# MPL3115A2_v10sch.net
KiCad netlist of a schematic drawn in EAGLE
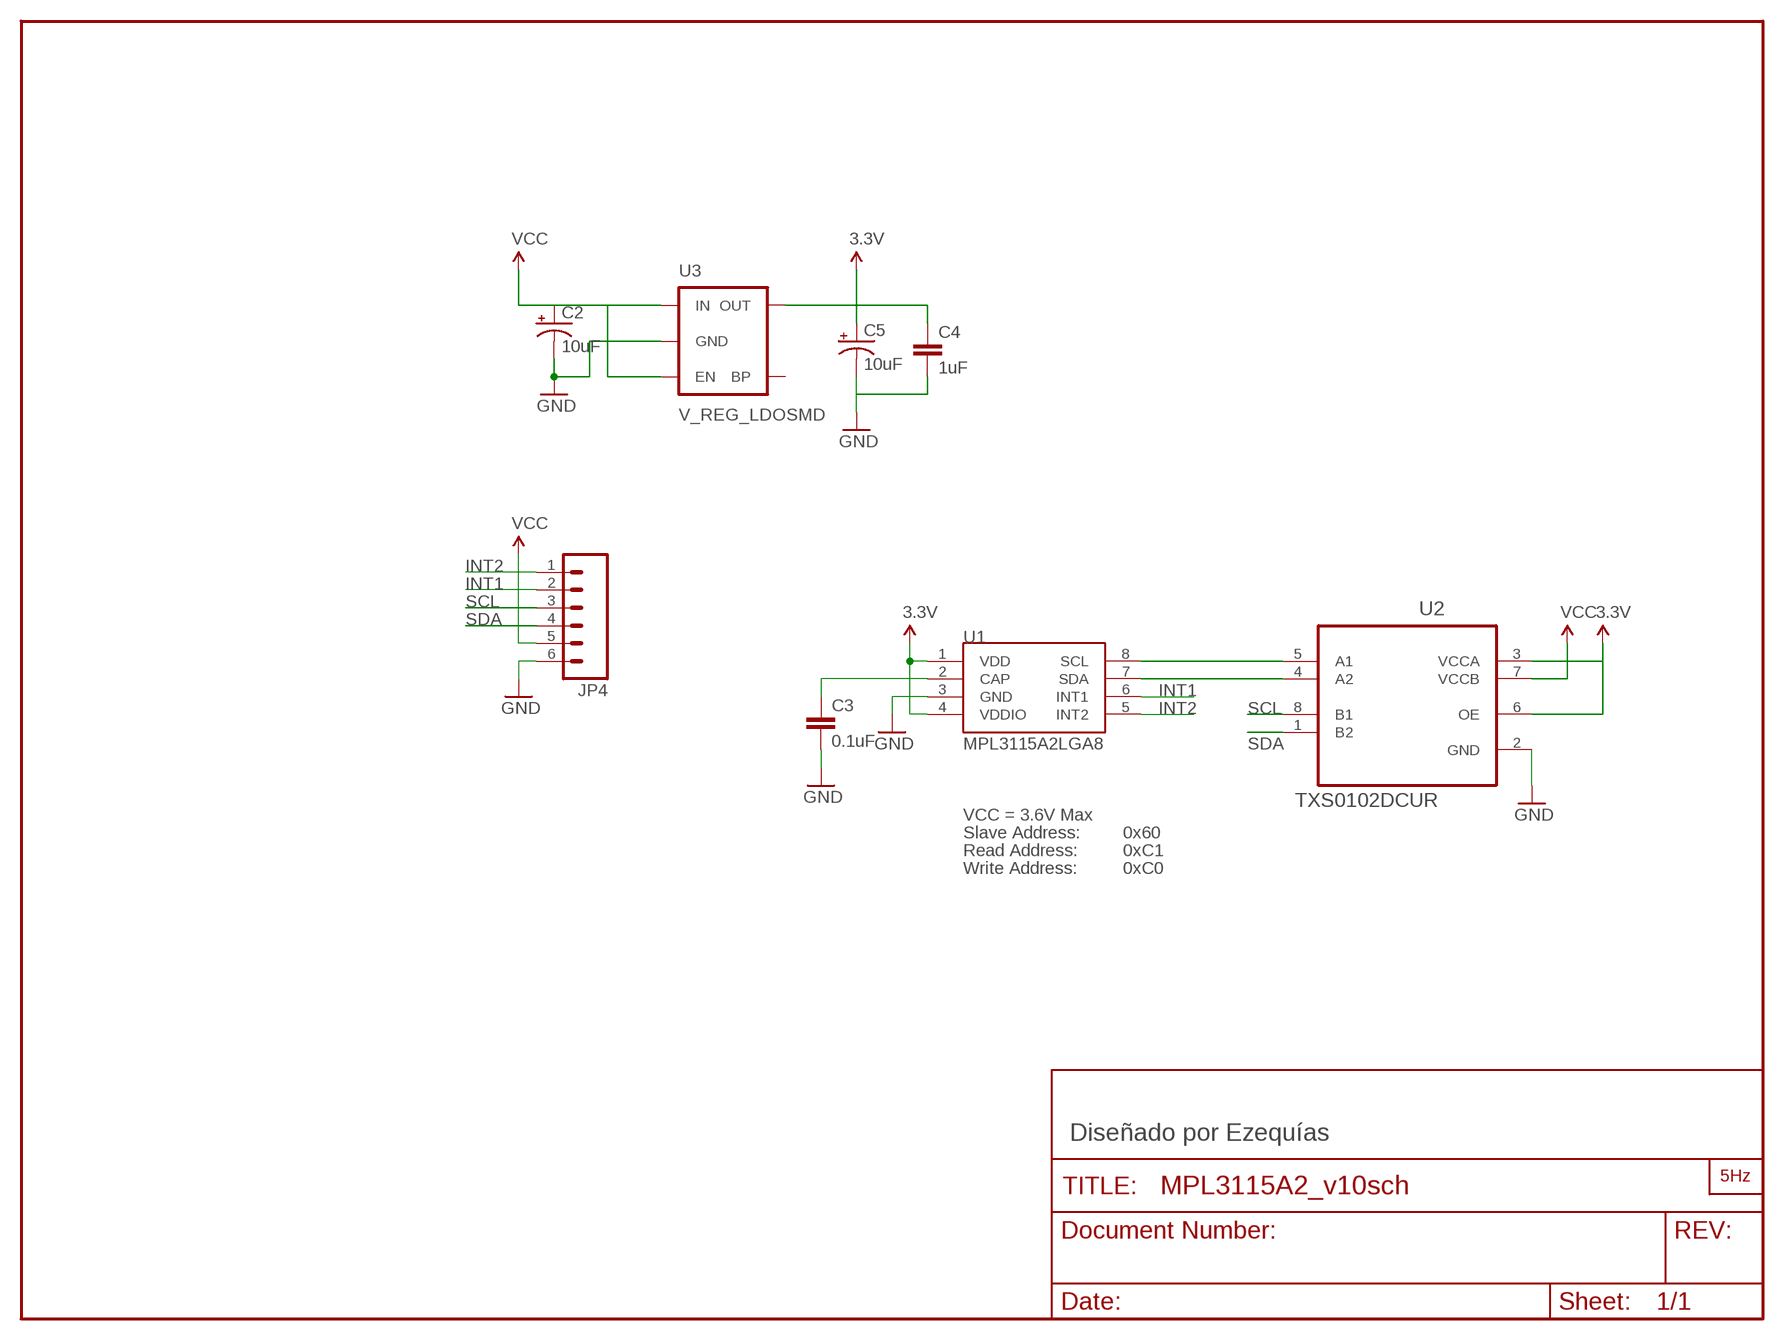
[diagram p0: schematic, sheet 1]

(export (version "E")
  (design (tool "Eeschema 10.0.6"))
  (components
    (comp (ref "C2")
      (value "10uF")
      (footprint "eagle-import:EIA3216")
      (libsource (lib "eagle-import") (part "CAP_POL1206"))
    )
    (comp (ref "C3")
      (value "0.1uF")
      (footprint "eagle-import:0402-CAP")
      (libsource (lib "eagle-import") (part "CAP0402-CAP"))
    )
    (comp (ref "C4")
      (value "1uF")
      (footprint "eagle-import:0402-CAP")
      (libsource (lib "eagle-import") (part "CAP0402-CAP"))
    )
    (comp (ref "C5")
      (value "10uF")
      (footprint "eagle-import:EIA3216")
      (libsource (lib "eagle-import") (part "CAP_POL1206"))
    )
    (comp (ref "JP4")
      (value "M06SIP")
      (footprint "eagle-import:1X06")
      (libsource (lib "eagle-import") (part "M06SIP"))
    )
    (comp (ref "U$2")
      (value "LOGO2_SILK5MM")
      (footprint "eagle-import:LOGO2_5MM")
      (libsource (lib "eagle-import") (part "LOGO2_SILK5MM"))
    )
    (comp (ref "U1")
      (value "MPL3115A2LGA8")
      (footprint "eagle-import:LGA8")
      (libsource (lib "eagle-import") (part "MPL3115A2LGA8"))
    )
    (comp (ref "U2")
      (value "TXS0102DCUR")
      (footprint "eagle-import:SOP50P310X90-8N")
      (libsource (lib "eagle-import") (part "TXS0102DCUR"))
    )
    (comp (ref "U3")
      (value "V_REG_LDOSMD")
      (footprint "eagle-import:SOT23-5")
      (libsource (lib "eagle-import") (part "V_REG_LDOSMD"))
    )
  )
  (nets
    (net (code "1") (name "/INT1") (class "Default")
      (node (ref "JP4") (pin "2") (pinfunction "2_2") (pintype "passive"))
      (node (ref "U1") (pin "6") (pinfunction "INT1_6") (pintype "bidirectional"))
    )
    (net (code "2") (name "/INT2") (class "Default")
      (node (ref "JP4") (pin "1") (pinfunction "1_1") (pintype "passive"))
      (node (ref "U1") (pin "5") (pinfunction "INT2_5") (pintype "bidirectional"))
    )
    (net (code "3") (name "/SCL") (class "Default")
      (node (ref "JP4") (pin "3") (pinfunction "3_3") (pintype "passive"))
      (node (ref "U2") (pin "8") (pinfunction "B1_8") (pintype "bidirectional"))
    )
    (net (code "4") (name "/SDA") (class "Default")
      (node (ref "JP4") (pin "4") (pinfunction "4_4") (pintype "passive"))
      (node (ref "U2") (pin "1") (pinfunction "B2_1") (pintype "bidirectional"))
    )
    (net (code "5") (name "3.3V") (class "Default")
      (node (ref "C4") (pin "1") (pinfunction "1_1") (pintype "passive"))
      (node (ref "C5") (pin "A") (pinfunction "+_A") (pintype "passive"))
      (node (ref "U1") (pin "1") (pinfunction "VDD_1") (pintype "bidirectional"))
      (node (ref "U1") (pin "4") (pinfunction "VDDIO_4") (pintype "bidirectional"))
      (node (ref "U2") (pin "3") (pinfunction "VCCA_3") (pintype "power_in"))
      (node (ref "U2") (pin "6") (pinfunction "OE_6") (pintype "input"))
      (node (ref "U3") (pin "5") (pinfunction "OUT_5") (pintype "passive"))
    )
    (net (code "6") (name "GND") (class "Default")
      (node (ref "C2") (pin "C") (pinfunction "-_C") (pintype "passive"))
      (node (ref "C3") (pin "2") (pinfunction "2_2") (pintype "passive"))
      (node (ref "C4") (pin "2") (pinfunction "2_2") (pintype "passive"))
      (node (ref "C5") (pin "C") (pinfunction "-_C") (pintype "passive"))
      (node (ref "JP4") (pin "6") (pinfunction "6_6") (pintype "passive"))
      (node (ref "U1") (pin "3") (pinfunction "GND_3") (pintype "bidirectional"))
      (node (ref "U2") (pin "2") (pinfunction "GND_2") (pintype "passive"))
      (node (ref "U3") (pin "2") (pinfunction "GND_2") (pintype "input"))
    )
    (net (code "7") (name "Net-(U1-CAP)") (class "Default")
      (node (ref "C3") (pin "1") (pinfunction "1_1") (pintype "passive"))
      (node (ref "U1") (pin "2") (pinfunction "CAP_2") (pintype "bidirectional"))
    )
    (net (code "8") (name "Net-(U1-SCL)") (class "Default")
      (node (ref "U1") (pin "8") (pinfunction "SCL_8") (pintype "bidirectional"))
      (node (ref "U2") (pin "5") (pinfunction "A1_5") (pintype "bidirectional"))
    )
    (net (code "9") (name "Net-(U1-SDA)") (class "Default")
      (node (ref "U1") (pin "7") (pinfunction "SDA_7") (pintype "bidirectional"))
      (node (ref "U2") (pin "4") (pinfunction "A2_4") (pintype "bidirectional"))
    )
    (net (code "10") (name "VCC") (class "Default")
      (node (ref "C2") (pin "A") (pinfunction "+_A") (pintype "passive"))
      (node (ref "JP4") (pin "5") (pinfunction "5_5") (pintype "passive"))
      (node (ref "U2") (pin "7") (pinfunction "VCCB_7") (pintype "power_in"))
      (node (ref "U3") (pin "1") (pinfunction "IN_1") (pintype "input"))
      (node (ref "U3") (pin "3") (pinfunction "EN_3") (pintype "input"))
    )
    (net (code "11") (name "unconnected-(U3-BP-Pad4)") (class "Default")
      (node (ref "U3") (pin "4") (pinfunction "BP_4") (pintype "input"))
    )
  )
)
